# Ranger_I2C.net
KiCad netlist of a schematic drawn in EAGLE
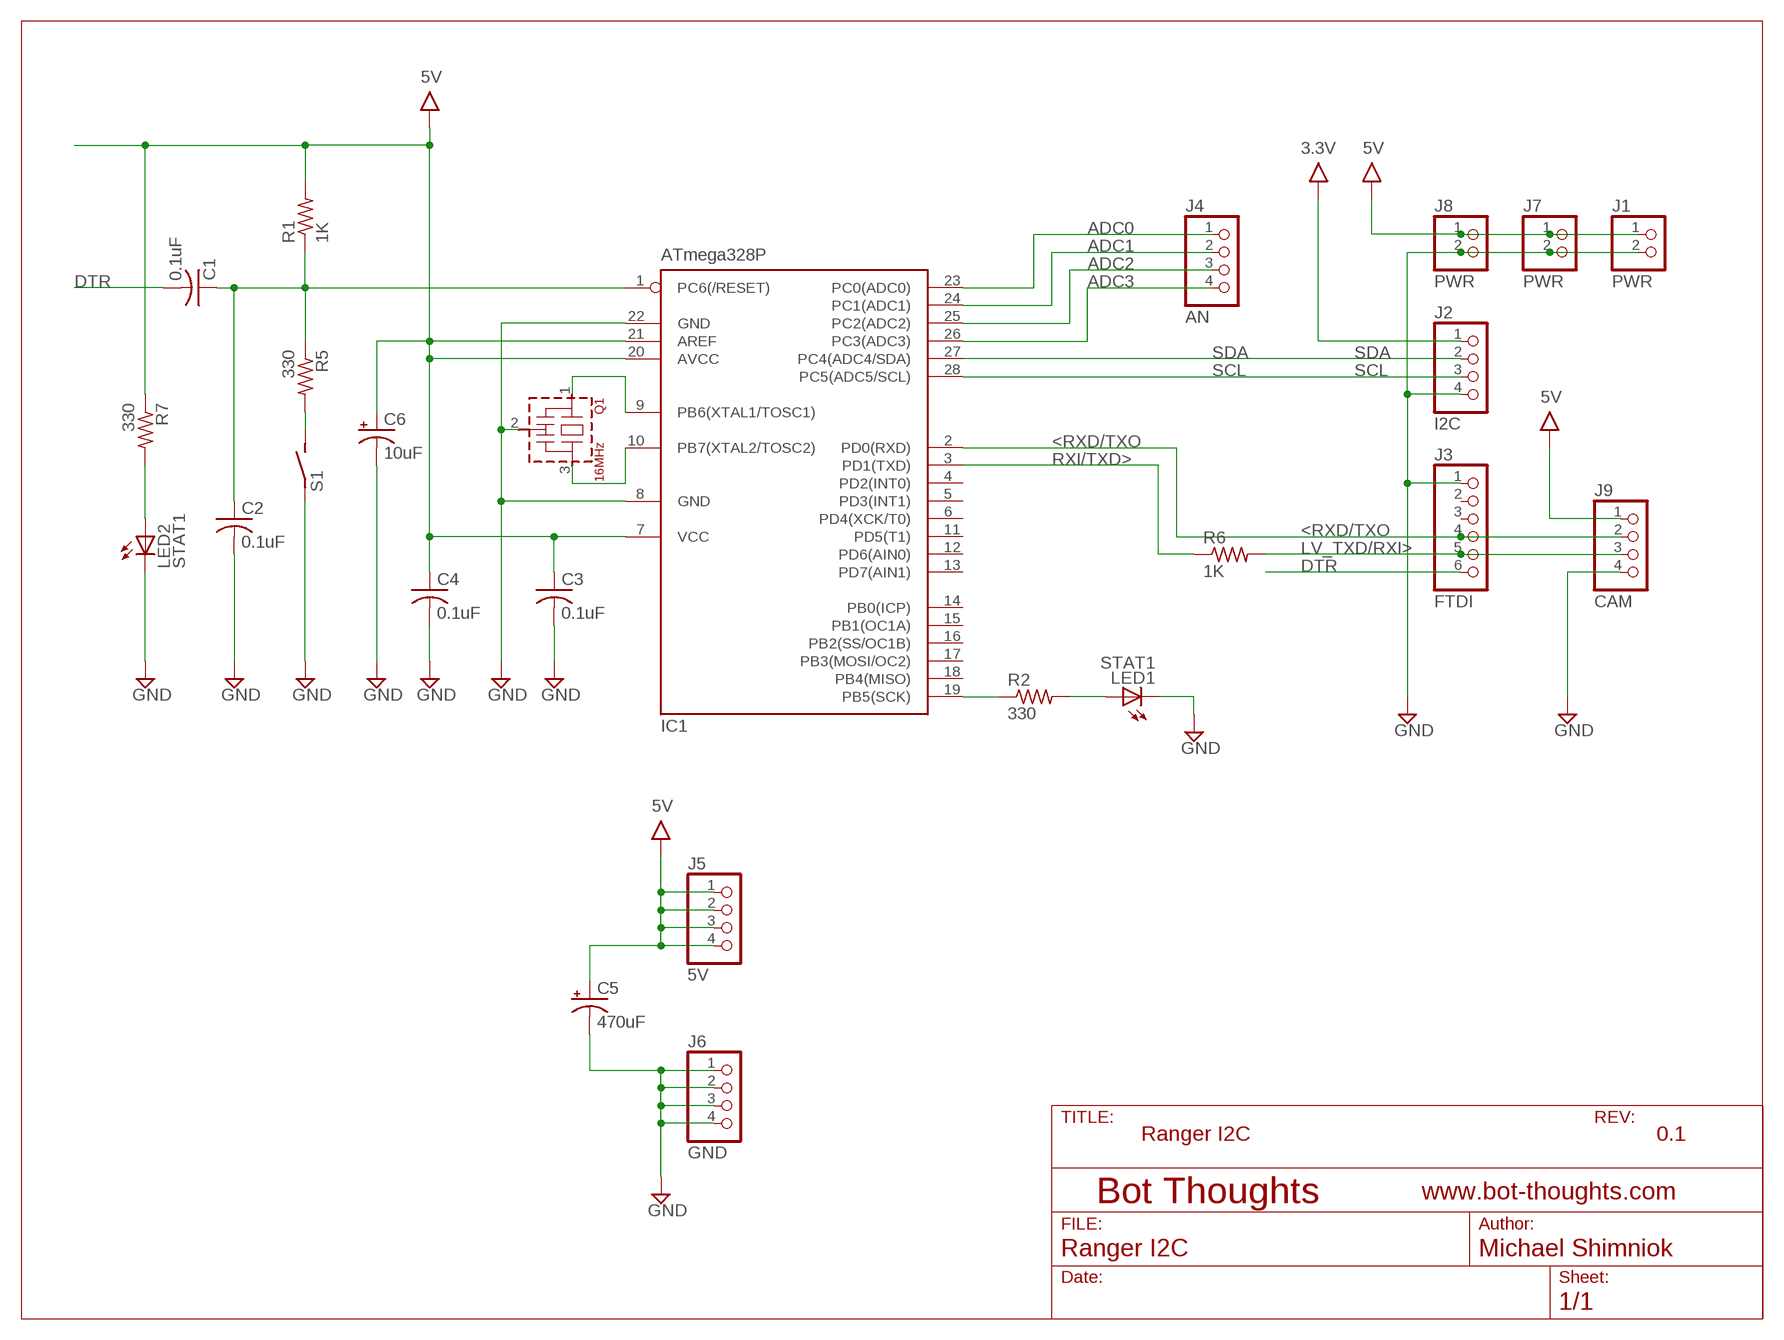
[diagram p0: schematic, sheet 1]

(export (version "E")
  (design (tool "Eeschema 10.0.6"))
  (components
    (comp (ref "C1")
      (value "0.1uF")
      (footprint "eagle-import:C050-024X044")
      (fields (field (name "PARTNO") "CC0603ZRY5V7BB104"))
      (libsource (lib "eagle-import") (part "C-US050-024X044"))
    )
    (comp (ref "C2")
      (value "0.1uF")
      (footprint "eagle-import:C050-024X044")
      (fields (field (name "PARTNO") "C1608X5R0J105K"))
      (libsource (lib "eagle-import") (part "C-US050-024X044"))
    )
    (comp (ref "C3")
      (value "0.1uF")
      (footprint "eagle-import:C050-024X044")
      (fields (field (name "PARTNO") "C1608X5R0J105K"))
      (libsource (lib "eagle-import") (part "C-US050-024X044"))
    )
    (comp (ref "C4")
      (value "0.1uF")
      (footprint "eagle-import:C050-024X044")
      (fields (field (name "PARTNO") "C1608X5R0J105K"))
      (libsource (lib "eagle-import") (part "C-US050-024X044"))
    )
    (comp (ref "C5")
      (value "470uF")
      (footprint "eagle-import:E2,5-6")
      (libsource (lib "eagle-import") (part "CPOL-USE2.5-6"))
    )
    (comp (ref "C6")
      (value "10uF")
      (footprint "eagle-import:E2,5-6")
      (libsource (lib "eagle-import") (part "CPOL-USE2.5-6"))
    )
    (comp (ref "IC1")
      (value "ATmega328P")
      (footprint "eagle-import:DIL28-3")
      (fields (field (name "PARTNO") "DEV-10524"))
      (libsource (lib "eagle-import") (part "MEGA8-P"))
    )
    (comp (ref "J1")
      (value "PWR")
      (footprint "eagle-import:1X02-S")
      (libsource (lib "eagle-import") (part "PINHD-1X02_2.54-S"))
    )
    (comp (ref "J2")
      (value "I2C")
      (footprint "eagle-import:1X04-S")
      (fields (field (name "PARTNO") "2211S-04G"))
      (libsource (lib "eagle-import") (part "PINHD-1X04_2.54-S"))
    )
    (comp (ref "J3")
      (value "FTDI")
      (footprint "eagle-import:1X06-S")
      (fields (field (name "PARTNO") "2211S-06G"))
      (libsource (lib "eagle-import") (part "PINHD-1X06_2.54-S"))
    )
    (comp (ref "J4")
      (value "AN")
      (footprint "eagle-import:1X04-S")
      (fields (field (name "PARTNO") "2211S-04G"))
      (libsource (lib "eagle-import") (part "PINHD-1X04_2.54-S"))
    )
    (comp (ref "J5")
      (value "5V")
      (footprint "eagle-import:1X04-S")
      (fields (field (name "PARTNO") "2211S-04G"))
      (libsource (lib "eagle-import") (part "PINHD-1X04_2.54-S"))
    )
    (comp (ref "J6")
      (value "GND")
      (footprint "eagle-import:1X04-S")
      (fields (field (name "PARTNO") "2211S-04G"))
      (libsource (lib "eagle-import") (part "PINHD-1X04_2.54-S"))
    )
    (comp (ref "J7")
      (value "PWR")
      (footprint "eagle-import:1X02-S")
      (libsource (lib "eagle-import") (part "PINHD-1X02_2.54-S"))
    )
    (comp (ref "J8")
      (value "PWR")
      (footprint "eagle-import:1X02-S")
      (libsource (lib "eagle-import") (part "PINHD-1X02_2.54-S"))
    )
    (comp (ref "J9")
      (value "CAM")
      (footprint "eagle-import:1X04-S")
      (fields (field (name "PARTNO") "2211S-04G"))
      (libsource (lib "eagle-import") (part "PINHD-1X04_2.54-S"))
    )
    (comp (ref "LED1")
      (value "STAT1")
      (footprint "eagle-import:LED3MM")
      (libsource (lib "eagle-import") (part "LED3MM"))
    )
    (comp (ref "LED2")
      (value "STAT1")
      (footprint "eagle-import:LED3MM")
      (libsource (lib "eagle-import") (part "LED3MM"))
    )
    (comp (ref "Q1")
      (value "16MHz")
      (footprint "eagle-import:CSTLS_G9")
      (fields (field (name "PARTNO") "AWCR-16.00MD"))
      (libsource (lib "eagle-import") (part "murata-resonators_CSTLS_G"))
    )
    (comp (ref "R1")
      (value "1K")
      (footprint "eagle-import:0204_5")
      (libsource (lib "eagle-import") (part "R-US_0204/5"))
    )
    (comp (ref "R2")
      (value "330")
      (footprint "eagle-import:0204_5")
      (fields (field (name "PARTNO") "CRCW0603330RJNEA"))
      (libsource (lib "eagle-import") (part "R-US_0204/5"))
    )
    (comp (ref "R5")
      (value "330")
      (footprint "eagle-import:0204_5")
      (fields (field (name "PARTNO") "CRCW0603330RJNEA"))
      (libsource (lib "eagle-import") (part "R-US_0204/5"))
    )
    (comp (ref "R6")
      (value "1K")
      (footprint "eagle-import:0204_5")
      (fields (field (name "PARTNO") "CRCW0603330RJNEA"))
      (libsource (lib "eagle-import") (part "R-US_0204/5"))
    )
    (comp (ref "R7")
      (value "330")
      (footprint "eagle-import:0204_5")
      (fields (field (name "PARTNO") "CRCW0603330RJNEA"))
      (libsource (lib "eagle-import") (part "R-US_0204/5"))
    )
    (comp (ref "S1")
      (value "RESET\\")
      (footprint "eagle-import:EVQ11X09")
      (fields (field (name "PARTNO") "SALVAGE"))
      (libsource (lib "eagle-import") (part "SPST2EVQ11X09"))
    )
  )
  (nets
    (net (code "1") (name "/<RXD{slash}TXO") (class "Default")
      (node (ref "IC1") (pin "2") (pinfunction "PD0(RXD)_2") (pintype "bidirectional"))
      (node (ref "J3") (pin "4") (pinfunction "4_4") (pintype "passive"))
      (node (ref "J9") (pin "2") (pinfunction "2_2") (pintype "passive"))
    )
    (net (code "2") (name "/ADC0") (class "Default")
      (node (ref "IC1") (pin "23") (pinfunction "PC0(ADC0)_23") (pintype "bidirectional"))
      (node (ref "J4") (pin "1") (pinfunction "1_1") (pintype "passive"))
    )
    (net (code "3") (name "/ADC1") (class "Default")
      (node (ref "IC1") (pin "24") (pinfunction "PC1(ADC1)_24") (pintype "bidirectional"))
      (node (ref "J4") (pin "2") (pinfunction "2_2") (pintype "passive"))
    )
    (net (code "4") (name "/ADC2") (class "Default")
      (node (ref "IC1") (pin "25") (pinfunction "PC2(ADC2)_25") (pintype "bidirectional"))
      (node (ref "J4") (pin "3") (pinfunction "3_3") (pintype "passive"))
    )
    (net (code "5") (name "/ADC3") (class "Default")
      (node (ref "IC1") (pin "26") (pinfunction "PC3(ADC3)_26") (pintype "bidirectional"))
      (node (ref "J4") (pin "4") (pinfunction "4_4") (pintype "passive"))
    )
    (net (code "6") (name "/DTR") (class "Default")
      (node (ref "C1") (pin "2") (pinfunction "2_2") (pintype "passive"))
      (node (ref "J3") (pin "6") (pinfunction "6_6") (pintype "passive"))
    )
    (net (code "7") (name "/LV_TXD{slash}RXI>") (class "Default")
      (node (ref "J3") (pin "5") (pinfunction "5_5") (pintype "passive"))
      (node (ref "J9") (pin "3") (pinfunction "3_3") (pintype "passive"))
      (node (ref "R6") (pin "2") (pinfunction "2_2") (pintype "passive"))
    )
    (net (code "8") (name "/RXI{slash}TXD>") (class "Default")
      (node (ref "IC1") (pin "3") (pinfunction "PD1(TXD)_3") (pintype "bidirectional"))
      (node (ref "R6") (pin "1") (pinfunction "1_1") (pintype "passive"))
    )
    (net (code "9") (name "/SCL") (class "Default")
      (node (ref "IC1") (pin "28") (pinfunction "PC5(ADC5/SCL)_28") (pintype "bidirectional"))
      (node (ref "J2") (pin "3") (pinfunction "3_3") (pintype "passive"))
    )
    (net (code "10") (name "/SDA") (class "Default")
      (node (ref "IC1") (pin "27") (pinfunction "PC4(ADC4/SDA)_27") (pintype "bidirectional"))
      (node (ref "J2") (pin "2") (pinfunction "2_2") (pintype "passive"))
    )
    (net (code "11") (name "3.3V") (class "Default")
      (node (ref "J2") (pin "1") (pinfunction "1_1") (pintype "passive"))
    )
    (net (code "12") (name "5V") (class "Default")
      (node (ref "C3") (pin "1") (pinfunction "1_1") (pintype "passive"))
      (node (ref "C4") (pin "1") (pinfunction "1_1") (pintype "passive"))
      (node (ref "C5") (pin "+") (pinfunction "+_+") (pintype "passive"))
      (node (ref "C6") (pin "+") (pinfunction "+_+") (pintype "passive"))
      (node (ref "IC1") (pin "20") (pinfunction "AVCC_20") (pintype "power_in"))
      (node (ref "IC1") (pin "21") (pinfunction "AREF_21") (pintype "passive"))
      (node (ref "IC1") (pin "7") (pinfunction "VCC_7") (pintype "power_in"))
      (node (ref "J1") (pin "1") (pinfunction "1_1") (pintype "passive"))
      (node (ref "J5") (pin "1") (pinfunction "1_1") (pintype "passive"))
      (node (ref "J5") (pin "2") (pinfunction "2_2") (pintype "passive"))
      (node (ref "J5") (pin "3") (pinfunction "3_3") (pintype "passive"))
      (node (ref "J5") (pin "4") (pinfunction "4_4") (pintype "passive"))
      (node (ref "J7") (pin "1") (pinfunction "1_1") (pintype "passive"))
      (node (ref "J8") (pin "1") (pinfunction "1_1") (pintype "passive"))
      (node (ref "J9") (pin "1") (pinfunction "1_1") (pintype "passive"))
      (node (ref "R1") (pin "2") (pinfunction "2_2") (pintype "passive"))
      (node (ref "R7") (pin "1") (pinfunction "1_1") (pintype "passive"))
    )
    (net (code "13") (name "GND") (class "Default")
      (node (ref "C2") (pin "2") (pinfunction "2_2") (pintype "passive"))
      (node (ref "C3") (pin "2") (pinfunction "2_2") (pintype "passive"))
      (node (ref "C4") (pin "2") (pinfunction "2_2") (pintype "passive"))
      (node (ref "C5") (pin "-") (pinfunction "-_-") (pintype "passive"))
      (node (ref "C6") (pin "-") (pinfunction "-_-") (pintype "passive"))
      (node (ref "IC1") (pin "22") (pinfunction "GND_22") (pintype "power_in"))
      (node (ref "IC1") (pin "8") (pinfunction "GND_8") (pintype "power_in"))
      (node (ref "J1") (pin "2") (pinfunction "2_2") (pintype "passive"))
      (node (ref "J2") (pin "4") (pinfunction "4_4") (pintype "passive"))
      (node (ref "J3") (pin "1") (pinfunction "1_1") (pintype "passive"))
      (node (ref "J6") (pin "1") (pinfunction "1_1") (pintype "passive"))
      (node (ref "J6") (pin "2") (pinfunction "2_2") (pintype "passive"))
      (node (ref "J6") (pin "3") (pinfunction "3_3") (pintype "passive"))
      (node (ref "J6") (pin "4") (pinfunction "4_4") (pintype "passive"))
      (node (ref "J7") (pin "2") (pinfunction "2_2") (pintype "passive"))
      (node (ref "J8") (pin "2") (pinfunction "2_2") (pintype "passive"))
      (node (ref "J9") (pin "4") (pinfunction "4_4") (pintype "passive"))
      (node (ref "LED1") (pin "K") (pinfunction "C_K") (pintype "passive"))
      (node (ref "LED2") (pin "K") (pinfunction "C_K") (pintype "passive"))
      (node (ref "Q1") (pin "2") (pinfunction "VSS_2") (pintype "power_in"))
      (node (ref "S1") (pin "1") (pinfunction "1_1") (pintype "passive"))
    )
    (net (code "14") (name "Net-(IC1-PB5(SCK))") (class "Default")
      (node (ref "IC1") (pin "19") (pinfunction "PB5(SCK)_19") (pintype "bidirectional"))
      (node (ref "R2") (pin "1") (pinfunction "1_1") (pintype "passive"))
    )
    (net (code "15") (name "Net-(IC1-PB6(XTAL1{slash}TOSC1))") (class "Default")
      (node (ref "IC1") (pin "9") (pinfunction "PB6(XTAL1/TOSC1)_9") (pintype "bidirectional"))
      (node (ref "Q1") (pin "1") (pinfunction "1_1") (pintype "output"))
    )
    (net (code "16") (name "Net-(IC1-PB7(XTAL2{slash}TOSC2))") (class "Default")
      (node (ref "IC1") (pin "10") (pinfunction "PB7(XTAL2/TOSC2)_10") (pintype "bidirectional"))
      (node (ref "Q1") (pin "3") (pinfunction "3_3") (pintype "input"))
    )
    (net (code "17") (name "Net-(IC1-PC6({slash}RESET))") (class "Default")
      (node (ref "C1") (pin "1") (pinfunction "1_1") (pintype "passive"))
      (node (ref "C2") (pin "1") (pinfunction "1_1") (pintype "passive"))
      (node (ref "IC1") (pin "1") (pinfunction "PC6(/RESET)_1") (pintype "bidirectional"))
      (node (ref "R1") (pin "1") (pinfunction "1_1") (pintype "passive"))
      (node (ref "R5") (pin "1") (pinfunction "1_1") (pintype "passive"))
    )
    (net (code "18") (name "Net-(LED1-PadA)") (class "Default")
      (node (ref "LED1") (pin "A") (pinfunction "A_A") (pintype "passive"))
      (node (ref "R2") (pin "2") (pinfunction "2_2") (pintype "passive"))
    )
    (net (code "19") (name "Net-(LED2-PadA)") (class "Default")
      (node (ref "LED2") (pin "A") (pinfunction "A_A") (pintype "passive"))
      (node (ref "R7") (pin "2") (pinfunction "2_2") (pintype "passive"))
    )
    (net (code "20") (name "Net-(R5-Pad2)") (class "Default")
      (node (ref "R5") (pin "2") (pinfunction "2_2") (pintype "passive"))
      (node (ref "S1") (pin "2") (pinfunction "2_2") (pintype "passive"))
    )
    (net (code "21") (name "unconnected-(IC1-PB0(ICP)-Pad14)") (class "Default")
      (node (ref "IC1") (pin "14") (pinfunction "PB0(ICP)_14") (pintype "bidirectional"))
    )
    (net (code "22") (name "unconnected-(IC1-PB1(OC1A)-Pad15)") (class "Default")
      (node (ref "IC1") (pin "15") (pinfunction "PB1(OC1A)_15") (pintype "bidirectional"))
    )
    (net (code "23") (name "unconnected-(IC1-PB2(SS{slash}OC1B)-Pad16)") (class "Default")
      (node (ref "IC1") (pin "16") (pinfunction "PB2(SS/OC1B)_16") (pintype "bidirectional"))
    )
    (net (code "24") (name "unconnected-(IC1-PB3(MOSI{slash}OC2)-Pad17)") (class "Default")
      (node (ref "IC1") (pin "17") (pinfunction "PB3(MOSI/OC2)_17") (pintype "bidirectional"))
    )
    (net (code "25") (name "unconnected-(IC1-PB4(MISO)-Pad18)") (class "Default")
      (node (ref "IC1") (pin "18") (pinfunction "PB4(MISO)_18") (pintype "bidirectional"))
    )
    (net (code "26") (name "unconnected-(IC1-PD2(INT0)-Pad4)") (class "Default")
      (node (ref "IC1") (pin "4") (pinfunction "PD2(INT0)_4") (pintype "bidirectional"))
    )
    (net (code "27") (name "unconnected-(IC1-PD3(INT1)-Pad5)") (class "Default")
      (node (ref "IC1") (pin "5") (pinfunction "PD3(INT1)_5") (pintype "bidirectional"))
    )
    (net (code "28") (name "unconnected-(IC1-PD4(XCK{slash}T0)-Pad6)") (class "Default")
      (node (ref "IC1") (pin "6") (pinfunction "PD4(XCK/T0)_6") (pintype "bidirectional"))
    )
    (net (code "29") (name "unconnected-(IC1-PD5(T1)-Pad11)") (class "Default")
      (node (ref "IC1") (pin "11") (pinfunction "PD5(T1)_11") (pintype "bidirectional"))
    )
    (net (code "30") (name "unconnected-(IC1-PD6(AIN0)-Pad12)") (class "Default")
      (node (ref "IC1") (pin "12") (pinfunction "PD6(AIN0)_12") (pintype "bidirectional"))
    )
    (net (code "31") (name "unconnected-(IC1-PD7(AIN1)-Pad13)") (class "Default")
      (node (ref "IC1") (pin "13") (pinfunction "PD7(AIN1)_13") (pintype "bidirectional"))
    )
    (net (code "32") (name "unconnected-(J3-Pad2)") (class "Default")
      (node (ref "J3") (pin "2") (pinfunction "2_2") (pintype "passive"))
    )
    (net (code "33") (name "unconnected-(J3-Pad3)") (class "Default")
      (node (ref "J3") (pin "3") (pinfunction "3_3") (pintype "passive"))
    )
  )
)
